# controller.net
KiCad netlist of a schematic drawn in EAGLE
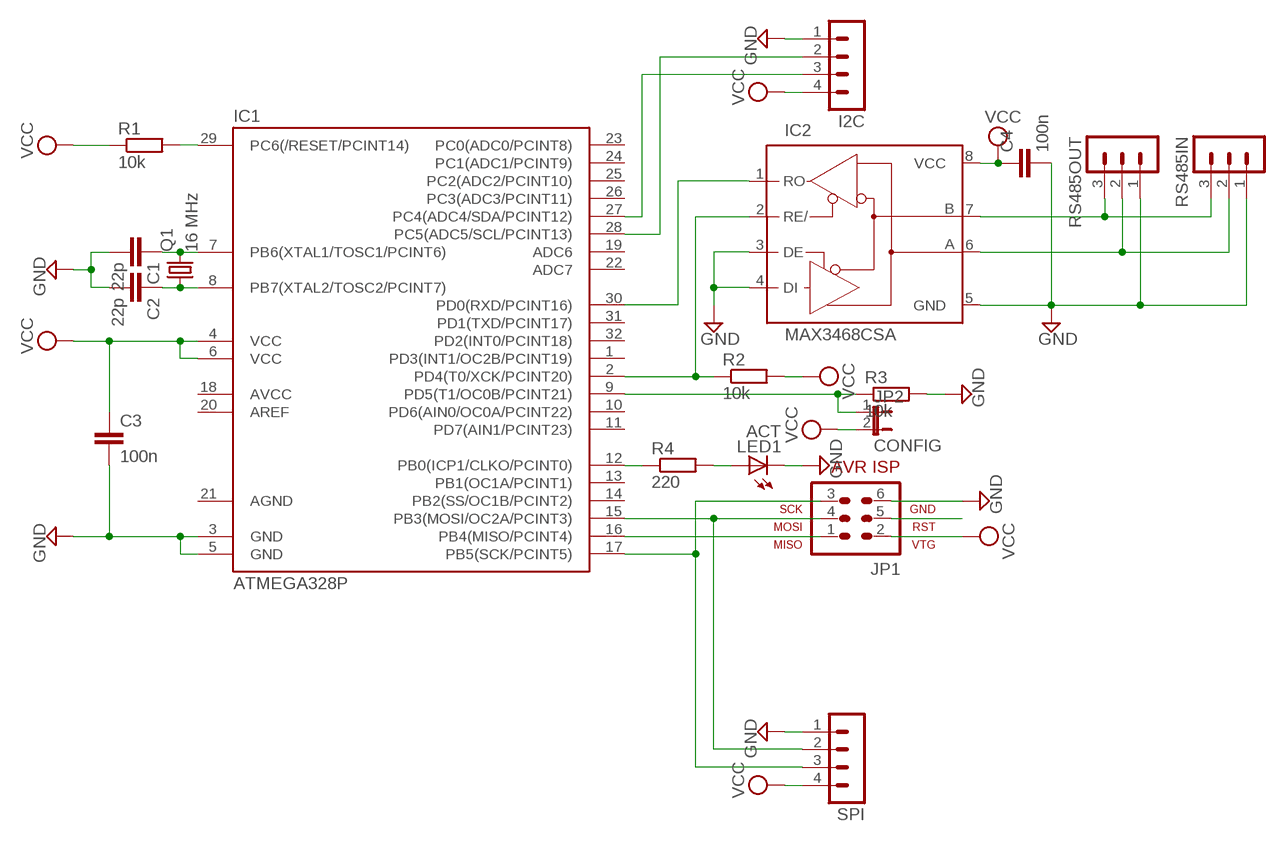
[diagram p0: schematic, sheet 1]

(export (version "E")
  (design (tool "Eeschema 10.0.6"))
  (components
    (comp (ref "C1")
      (value "22p")
      (footprint "eagle-import:C0805")
      (libsource (lib "eagle-import") (part "C-EUC0805"))
    )
    (comp (ref "C2")
      (value "22p")
      (footprint "eagle-import:C0805")
      (libsource (lib "eagle-import") (part "C-EUC0805"))
    )
    (comp (ref "C3")
      (value "100n")
      (footprint "eagle-import:C0805")
      (libsource (lib "eagle-import") (part "C-EUC0805"))
    )
    (comp (ref "C4")
      (value "100n")
      (footprint "eagle-import:C0805")
      (libsource (lib "eagle-import") (part "C-EUC0805"))
    )
    (comp (ref "I2C")
      (value "MA04-1")
      (footprint "eagle-import:MA04-1")
      (libsource (lib "eagle-import") (part "MA04-1"))
    )
    (comp (ref "IC1")
      (value "ATMEGA328P")
      (footprint "eagle-import:TQFP32-08")
      (libsource (lib "eagle-import") (part "MEGA48/88/168-AU"))
    )
    (comp (ref "IC2")
      (value "MAX3468CSA")
      (footprint "eagle-import:SO08")
      (fields (field (name "MPN") "MAX3468CSA+"))
      (libsource (lib "eagle-import") (part "MAX34SA68C"))
    )
    (comp (ref "JP1")
      (value "AVR-ISP-6")
      (footprint "eagle-import:AVR-ISP-6")
      (libsource (lib "eagle-import") (part "AVR-ISP-6"))
    )
    (comp (ref "JP2")
      (value "CONFIG")
      (footprint "eagle-import:JP1")
      (libsource (lib "eagle-import") (part "JP1E"))
    )
    (comp (ref "LED1")
      (value "ACT")
      (footprint "eagle-import:SML0603")
      (libsource (lib "eagle-import") (part "LEDSML0603"))
    )
    (comp (ref "Q1")
      (value "16 MHz")
      (footprint "eagle-import:MT")
      (libsource (lib "eagle-import") (part "CRYSTALMT"))
    )
    (comp (ref "R1")
      (value "10k")
      (footprint "eagle-import:R0805")
      (libsource (lib "eagle-import") (part "R-EU_R0805"))
    )
    (comp (ref "R2")
      (value "10k")
      (footprint "eagle-import:R0805")
      (libsource (lib "eagle-import") (part "R-EU_R0805"))
    )
    (comp (ref "R3")
      (value "10k")
      (footprint "eagle-import:R0805")
      (libsource (lib "eagle-import") (part "R-EU_R0805"))
    )
    (comp (ref "R4")
      (value "220")
      (footprint "eagle-import:R0805")
      (libsource (lib "eagle-import") (part "R-EU_R0805"))
    )
    (comp (ref "RS485IN")
      (value "MA03-1")
      (footprint "eagle-import:MA03-1")
      (libsource (lib "eagle-import") (part "MA03-1"))
    )
    (comp (ref "RS485OUT")
      (value "MA03-1")
      (footprint "eagle-import:MA03-1")
      (libsource (lib "eagle-import") (part "MA03-1"))
    )
    (comp (ref "SPI")
      (value "MA04-1")
      (footprint "eagle-import:MA04-1")
      (libsource (lib "eagle-import") (part "MA04-1"))
    )
  )
  (nets
    (net (code "1") (name "/AGND") (class "Default")
      (node (ref "IC1") (pin "21") (pinfunction "AGND_21") (pintype "power_in"))
    )
    (net (code "2") (name "/RESET") (class "Default")
      (node (ref "IC1") (pin "29") (pinfunction "PC6(/RESET/PCINT14)_29") (pintype "bidirectional"))
      (node (ref "JP1") (pin "5") (pinfunction "5_5") (pintype "passive"))
      (node (ref "R1") (pin "2") (pinfunction "2_2") (pintype "passive"))
    )
    (net (code "3") (name "GND") (class "Default")
      (node (ref "C1") (pin "2") (pinfunction "2_2") (pintype "passive"))
      (node (ref "C2") (pin "2") (pinfunction "2_2") (pintype "passive"))
      (node (ref "C3") (pin "2") (pinfunction "2_2") (pintype "passive"))
      (node (ref "C4") (pin "2") (pinfunction "2_2") (pintype "passive"))
      (node (ref "I2C") (pin "1") (pinfunction "1_1") (pintype "passive"))
      (node (ref "IC1") (pin "3") (pinfunction "GND_3") (pintype "power_in"))
      (node (ref "IC1") (pin "5") (pinfunction "GND_5") (pintype "power_in"))
      (node (ref "IC2") (pin "3") (pinfunction "DE_3") (pintype "input"))
      (node (ref "IC2") (pin "4") (pinfunction "DI_4") (pintype "input"))
      (node (ref "IC2") (pin "5") (pinfunction "GND_5") (pintype "power_in"))
      (node (ref "JP1") (pin "6") (pinfunction "6_6") (pintype "passive"))
      (node (ref "LED1") (pin "C") (pinfunction "C_C") (pintype "passive"))
      (node (ref "R3") (pin "2") (pinfunction "2_2") (pintype "passive"))
      (node (ref "RS485IN") (pin "1") (pinfunction "1_1") (pintype "passive"))
      (node (ref "RS485OUT") (pin "1") (pinfunction "1_1") (pintype "passive"))
      (node (ref "SPI") (pin "1") (pinfunction "1_1") (pintype "passive"))
    )
    (net (code "4") (name "Net-(IC1-PB0(ICP1{slash}CLKO{slash}PCINT0))") (class "Default")
      (node (ref "IC1") (pin "12") (pinfunction "PB0(ICP1/CLKO/PCINT0)_12") (pintype "bidirectional"))
      (node (ref "R4") (pin "1") (pinfunction "1_1") (pintype "passive"))
    )
    (net (code "5") (name "Net-(IC1-PB3(MOSI{slash}OC2A{slash}PCINT3))") (class "Default")
      (node (ref "IC1") (pin "15") (pinfunction "PB3(MOSI/OC2A/PCINT3)_15") (pintype "bidirectional"))
      (node (ref "JP1") (pin "4") (pinfunction "4_4") (pintype "passive"))
      (node (ref "SPI") (pin "2") (pinfunction "2_2") (pintype "passive"))
    )
    (net (code "6") (name "Net-(IC1-PB4(MISO{slash}PCINT4))") (class "Default")
      (node (ref "IC1") (pin "16") (pinfunction "PB4(MISO/PCINT4)_16") (pintype "bidirectional"))
      (node (ref "JP1") (pin "1") (pinfunction "1_1") (pintype "passive"))
    )
    (net (code "7") (name "Net-(IC1-PB5(SCK{slash}PCINT5))") (class "Default")
      (node (ref "IC1") (pin "17") (pinfunction "PB5(SCK/PCINT5)_17") (pintype "bidirectional"))
      (node (ref "JP1") (pin "3") (pinfunction "3_3") (pintype "passive"))
      (node (ref "SPI") (pin "3") (pinfunction "3_3") (pintype "passive"))
    )
    (net (code "8") (name "Net-(IC1-PB6(XTAL1{slash}TOSC1{slash}PCINT6))") (class "Default")
      (node (ref "C1") (pin "1") (pinfunction "1_1") (pintype "passive"))
      (node (ref "IC1") (pin "7") (pinfunction "PB6(XTAL1/TOSC1/PCINT6)_7") (pintype "bidirectional"))
      (node (ref "Q1") (pin "P3") (pinfunction "2_P3") (pintype "passive"))
    )
    (net (code "9") (name "Net-(IC1-PB7(XTAL2{slash}TOSC2{slash}PCINT7))") (class "Default")
      (node (ref "C2") (pin "1") (pinfunction "1_1") (pintype "passive"))
      (node (ref "IC1") (pin "8") (pinfunction "PB7(XTAL2/TOSC2/PCINT7)_8") (pintype "bidirectional"))
      (node (ref "Q1") (pin "P1") (pinfunction "1_P1") (pintype "passive"))
    )
    (net (code "10") (name "Net-(IC1-PC4(ADC4{slash}SDA{slash}PCINT12))") (class "Default")
      (node (ref "I2C") (pin "3") (pinfunction "3_3") (pintype "passive"))
      (node (ref "IC1") (pin "27") (pinfunction "PC4(ADC4/SDA/PCINT12)_27") (pintype "bidirectional"))
    )
    (net (code "11") (name "Net-(IC1-PC5(ADC5{slash}SCL{slash}PCINT13))") (class "Default")
      (node (ref "I2C") (pin "2") (pinfunction "2_2") (pintype "passive"))
      (node (ref "IC1") (pin "28") (pinfunction "PC5(ADC5/SCL/PCINT13)_28") (pintype "bidirectional"))
    )
    (net (code "12") (name "Net-(IC1-PD0(RXD{slash}PCINT16))") (class "Default")
      (node (ref "IC1") (pin "30") (pinfunction "PD0(RXD/PCINT16)_30") (pintype "bidirectional"))
      (node (ref "IC2") (pin "1") (pinfunction "RO_1") (pintype "output"))
    )
    (net (code "13") (name "Net-(IC1-PD4(T0{slash}XCK{slash}PCINT20))") (class "Default")
      (node (ref "IC1") (pin "2") (pinfunction "PD4(T0/XCK/PCINT20)_2") (pintype "bidirectional"))
      (node (ref "IC2") (pin "2") (pinfunction "RE/_2") (pintype "input"))
      (node (ref "R2") (pin "1") (pinfunction "1_1") (pintype "passive"))
    )
    (net (code "14") (name "Net-(IC1-PD5(T1{slash}OC0B{slash}PCINT21))") (class "Default")
      (node (ref "IC1") (pin "9") (pinfunction "PD5(T1/OC0B/PCINT21)_9") (pintype "bidirectional"))
      (node (ref "JP2") (pin "1") (pinfunction "1_1") (pintype "passive"))
      (node (ref "R3") (pin "1") (pinfunction "1_1") (pintype "passive"))
    )
    (net (code "15") (name "Net-(IC2-A)") (class "Default")
      (node (ref "IC2") (pin "6") (pinfunction "A_6") (pintype "passive"))
      (node (ref "RS485IN") (pin "2") (pinfunction "2_2") (pintype "passive"))
      (node (ref "RS485OUT") (pin "2") (pinfunction "2_2") (pintype "passive"))
    )
    (net (code "16") (name "Net-(IC2-B)") (class "Default")
      (node (ref "IC2") (pin "7") (pinfunction "B_7") (pintype "passive"))
      (node (ref "RS485IN") (pin "3") (pinfunction "3_3") (pintype "passive"))
      (node (ref "RS485OUT") (pin "3") (pinfunction "3_3") (pintype "passive"))
    )
    (net (code "17") (name "Net-(LED1-PadA)") (class "Default")
      (node (ref "LED1") (pin "A") (pinfunction "A_A") (pintype "passive"))
      (node (ref "R4") (pin "2") (pinfunction "2_2") (pintype "passive"))
    )
    (net (code "18") (name "VCC") (class "Default")
      (node (ref "C3") (pin "1") (pinfunction "1_1") (pintype "passive"))
      (node (ref "C4") (pin "1") (pinfunction "1_1") (pintype "passive"))
      (node (ref "I2C") (pin "4") (pinfunction "4_4") (pintype "passive"))
      (node (ref "IC1") (pin "4") (pinfunction "VCC_4") (pintype "power_in"))
      (node (ref "IC1") (pin "6") (pinfunction "VCC_6") (pintype "power_in"))
      (node (ref "IC2") (pin "8") (pinfunction "VCC_8") (pintype "power_in"))
      (node (ref "JP1") (pin "2") (pinfunction "2_2") (pintype "passive"))
      (node (ref "JP2") (pin "2") (pinfunction "2_2") (pintype "passive"))
      (node (ref "R1") (pin "1") (pinfunction "1_1") (pintype "passive"))
      (node (ref "R2") (pin "2") (pinfunction "2_2") (pintype "passive"))
      (node (ref "SPI") (pin "4") (pinfunction "4_4") (pintype "passive"))
    )
    (net (code "19") (name "unconnected-(IC1-ADC6-Pad19)") (class "Default")
      (node (ref "IC1") (pin "19") (pinfunction "ADC6_19") (pintype "passive"))
    )
    (net (code "20") (name "unconnected-(IC1-ADC7-Pad22)") (class "Default")
      (node (ref "IC1") (pin "22") (pinfunction "ADC7_22") (pintype "passive"))
    )
    (net (code "21") (name "unconnected-(IC1-AREF-Pad20)") (class "Default")
      (node (ref "IC1") (pin "20") (pinfunction "AREF_20") (pintype "passive"))
    )
    (net (code "22") (name "unconnected-(IC1-AVCC-Pad18)") (class "Default")
      (node (ref "IC1") (pin "18") (pinfunction "AVCC_18") (pintype "passive"))
    )
    (net (code "23") (name "unconnected-(IC1-PB1(OC1A{slash}PCINT1)-Pad13)") (class "Default")
      (node (ref "IC1") (pin "13") (pinfunction "PB1(OC1A/PCINT1)_13") (pintype "bidirectional"))
    )
    (net (code "24") (name "unconnected-(IC1-PB2(SS{slash}OC1B{slash}PCINT2)-Pad14)") (class "Default")
      (node (ref "IC1") (pin "14") (pinfunction "PB2(SS/OC1B/PCINT2)_14") (pintype "bidirectional"))
    )
    (net (code "25") (name "unconnected-(IC1-PC0(ADC0{slash}PCINT8)-Pad23)") (class "Default")
      (node (ref "IC1") (pin "23") (pinfunction "PC0(ADC0/PCINT8)_23") (pintype "bidirectional"))
    )
    (net (code "26") (name "unconnected-(IC1-PC1(ADC1{slash}PCINT9)-Pad24)") (class "Default")
      (node (ref "IC1") (pin "24") (pinfunction "PC1(ADC1/PCINT9)_24") (pintype "bidirectional"))
    )
    (net (code "27") (name "unconnected-(IC1-PC2(ADC2{slash}PCINT10)-Pad25)") (class "Default")
      (node (ref "IC1") (pin "25") (pinfunction "PC2(ADC2/PCINT10)_25") (pintype "bidirectional"))
    )
    (net (code "28") (name "unconnected-(IC1-PC3(ADC3{slash}PCINT11)-Pad26)") (class "Default")
      (node (ref "IC1") (pin "26") (pinfunction "PC3(ADC3/PCINT11)_26") (pintype "bidirectional"))
    )
    (net (code "29") (name "unconnected-(IC1-PD1(TXD{slash}PCINT17)-Pad31)") (class "Default")
      (node (ref "IC1") (pin "31") (pinfunction "PD1(TXD/PCINT17)_31") (pintype "bidirectional"))
    )
    (net (code "30") (name "unconnected-(IC1-PD2(INT0{slash}PCINT18)-Pad32)") (class "Default")
      (node (ref "IC1") (pin "32") (pinfunction "PD2(INT0/PCINT18)_32") (pintype "bidirectional"))
    )
    (net (code "31") (name "unconnected-(IC1-PD3(INT1{slash}OC2B{slash}PCINT19)-Pad1)") (class "Default")
      (node (ref "IC1") (pin "1") (pinfunction "PD3(INT1/OC2B/PCINT19)_1") (pintype "bidirectional"))
    )
    (net (code "32") (name "unconnected-(IC1-PD6(AIN0{slash}OC0A{slash}PCINT22)-Pad10)") (class "Default")
      (node (ref "IC1") (pin "10") (pinfunction "PD6(AIN0/OC0A/PCINT22)_10") (pintype "bidirectional"))
    )
    (net (code "33") (name "unconnected-(IC1-PD7(AIN1{slash}PCINT23)-Pad11)") (class "Default")
      (node (ref "IC1") (pin "11") (pinfunction "PD7(AIN1/PCINT23)_11") (pintype "bidirectional"))
    )
  )
)
